# Atom.net
KiCad netlist of a schematic drawn in Altium Designer
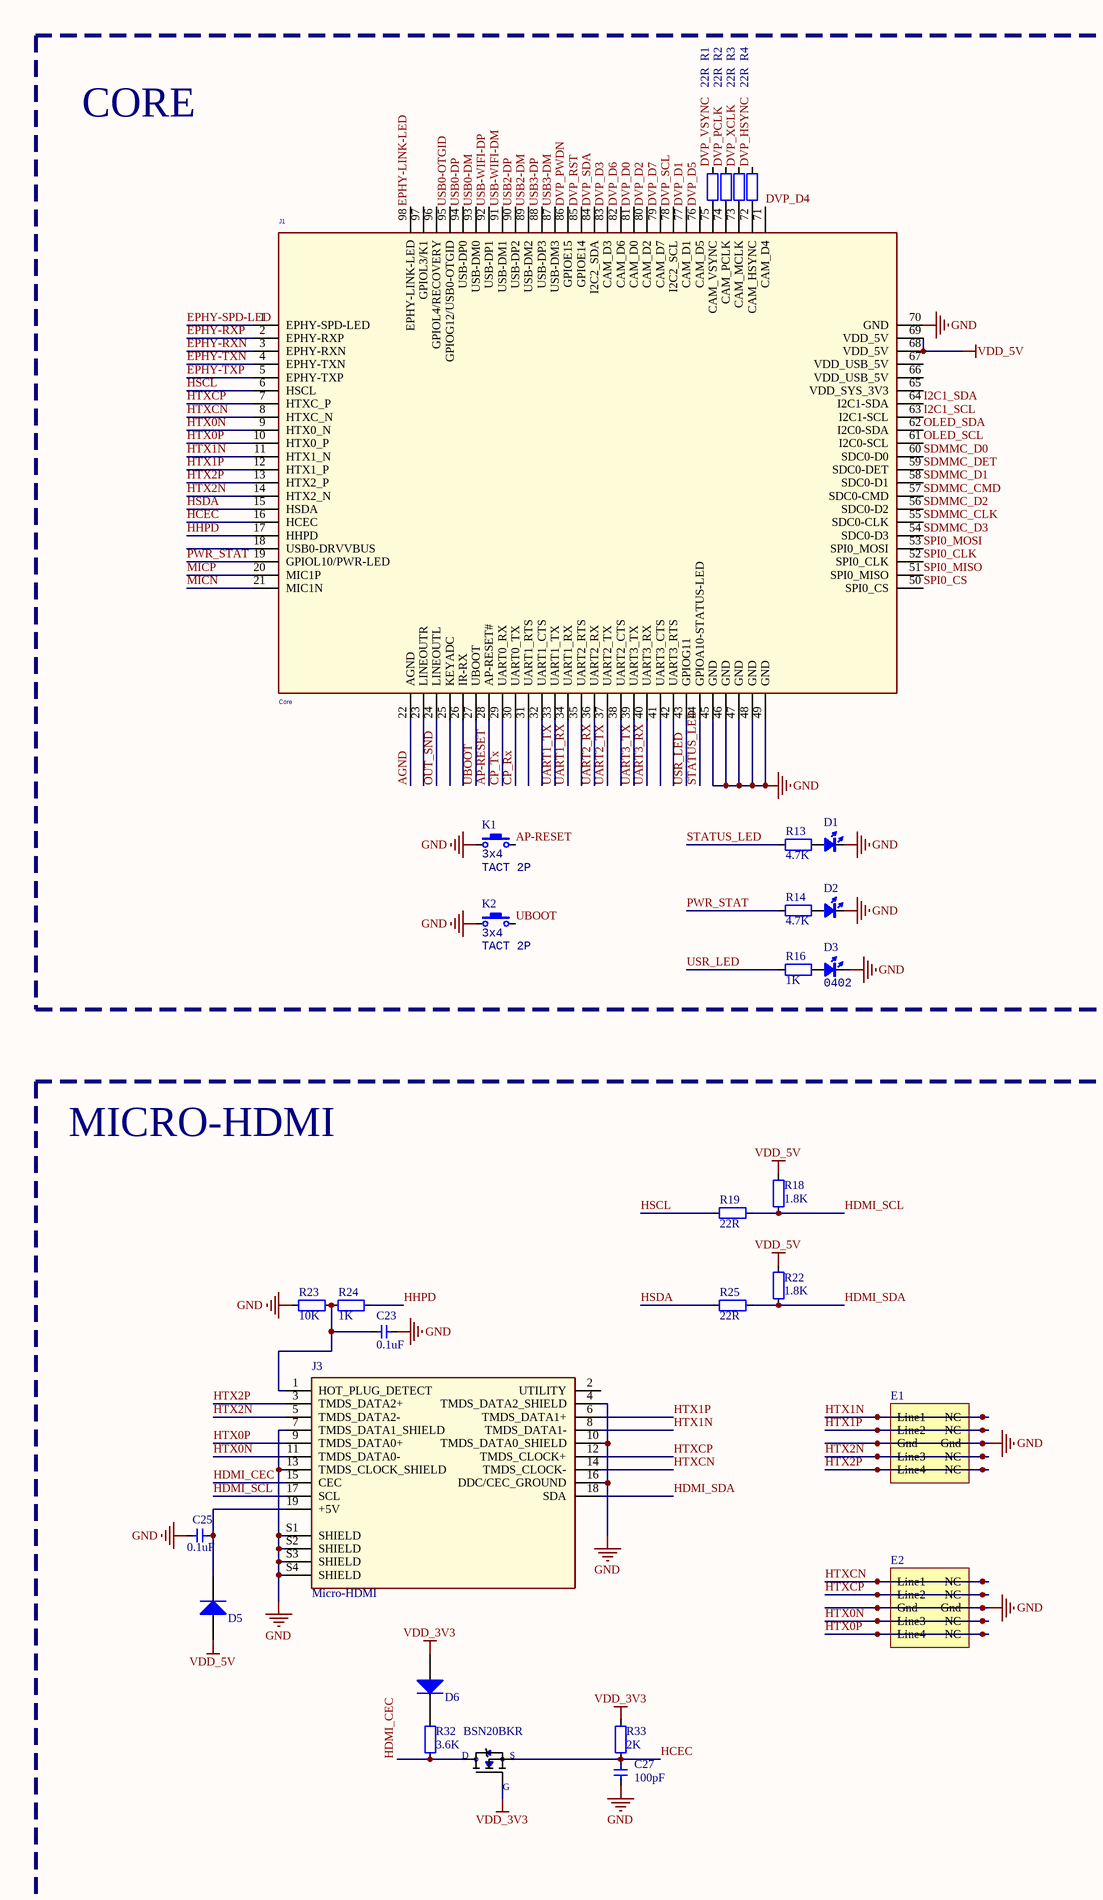
[diagram p0: Atom.SchDoc, left]
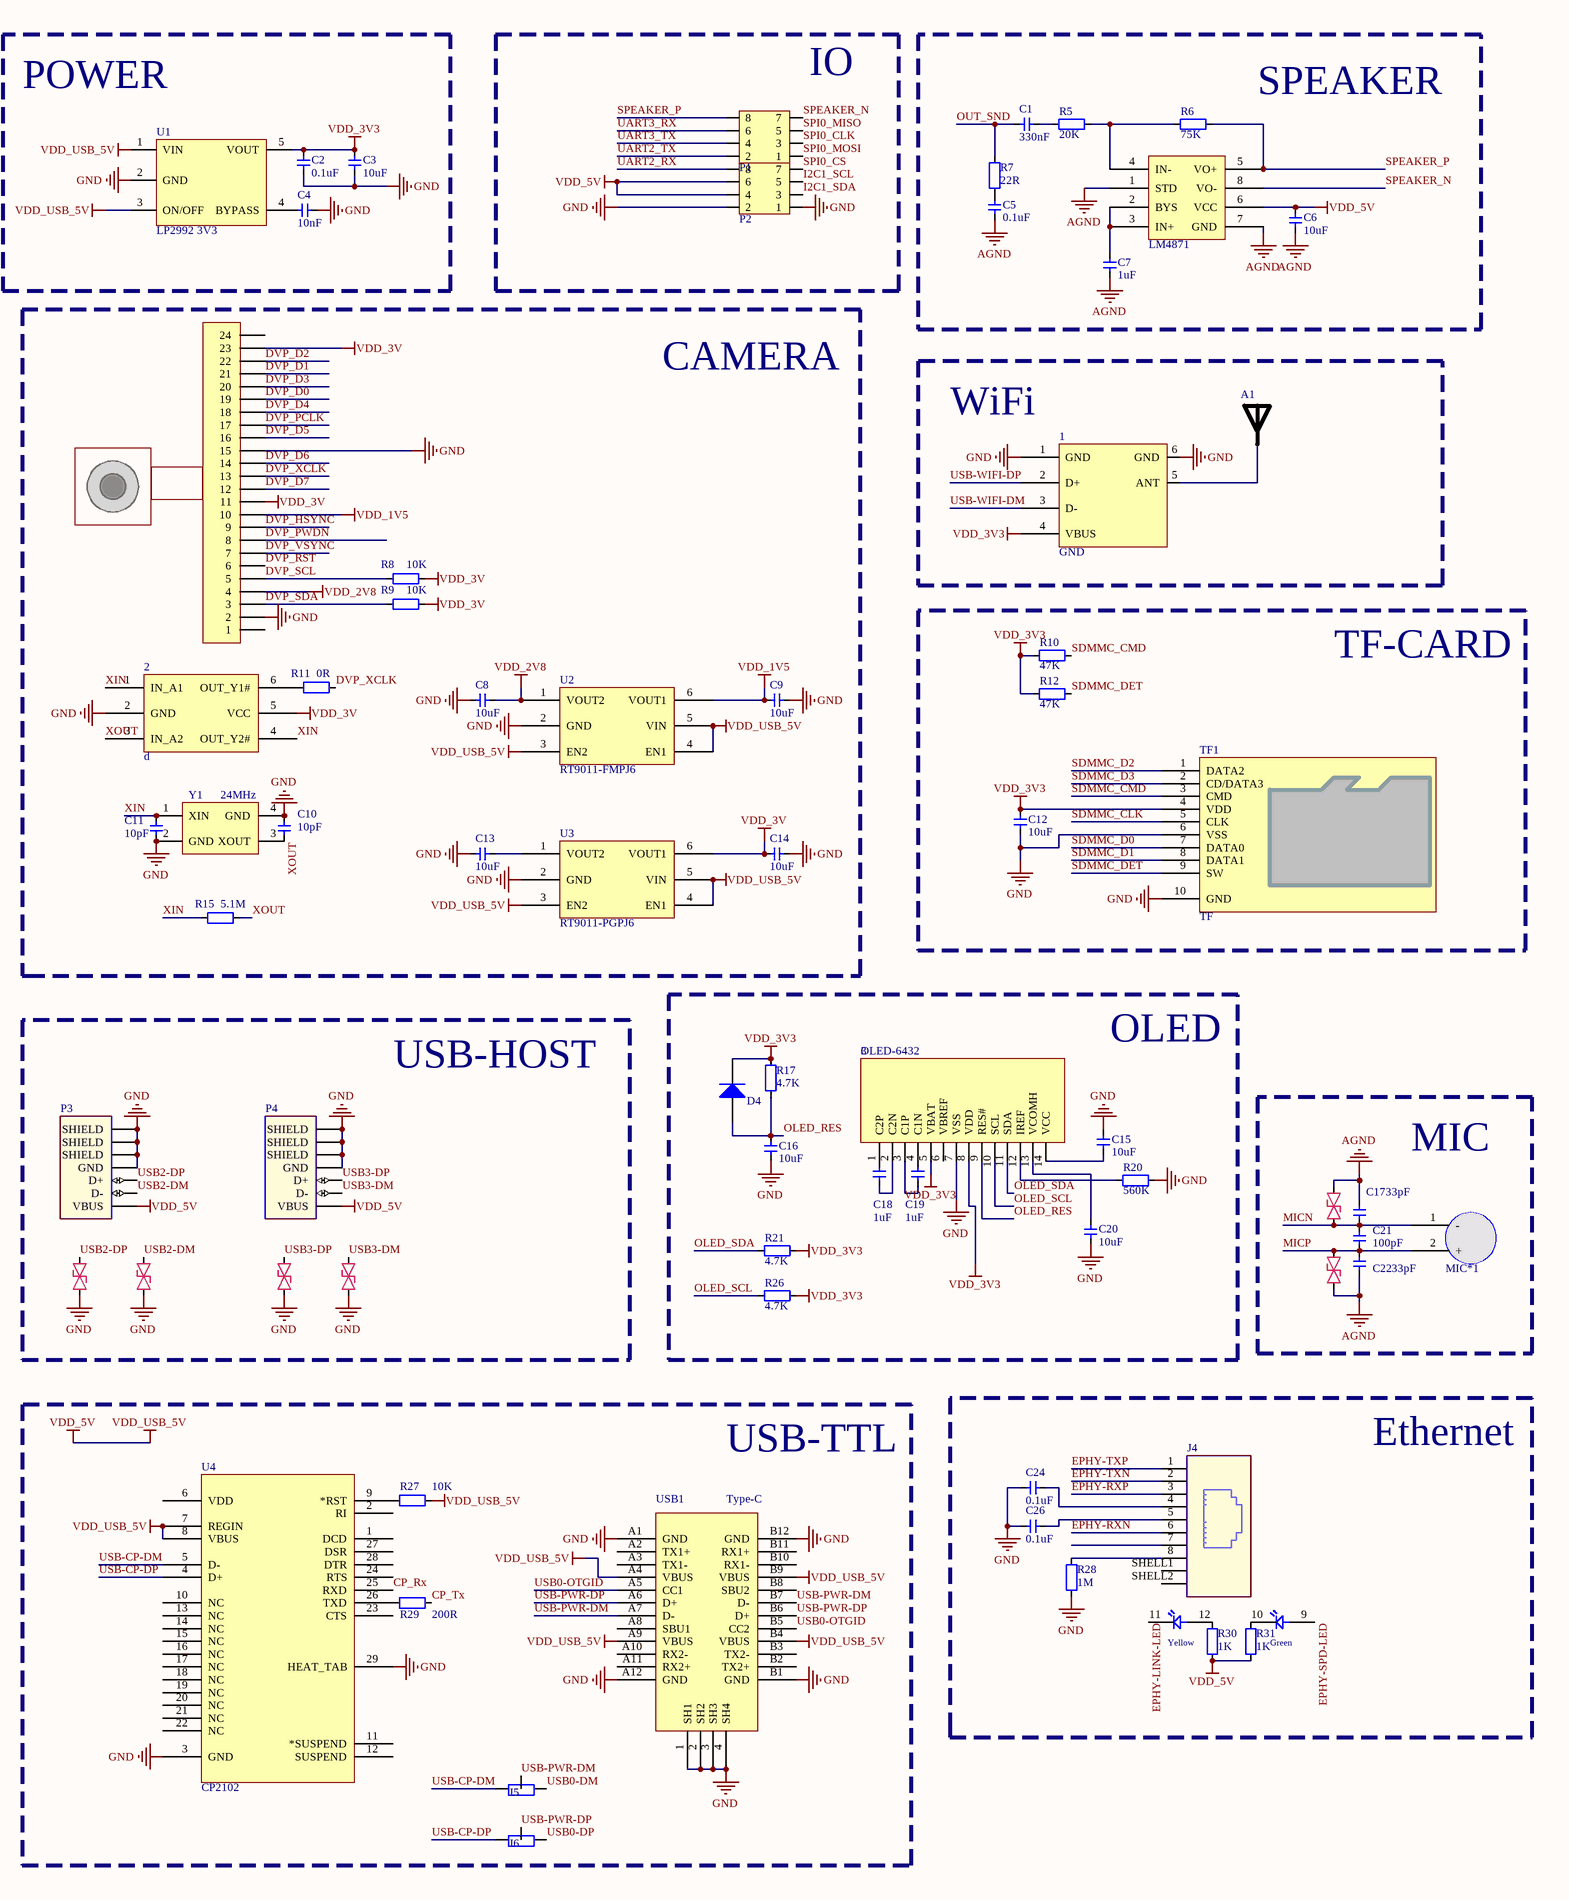
[diagram p1: Atom.SchDoc, right]

(export (version "E")
  (design (tool "Eeschema 10.0.6"))
  (components
    (comp (ref "*1") (value "LM4871") (footprint "MSOP-8") (libsource (lib "MyPcbLib") (part "LM4871")))
    (comp (ref "1")
      (value "GND")
      (footprint "USB-WiFI-ANT")
      (libsource (lib "MyPcbLib") (part "USB-WiFi-ANT"))
    )
    (comp (ref "2") (value "d") (footprint "SOT363-6") (libsource (lib "MyPcbLib") (part "NL27WZU04DF")))
    (comp (ref "3")
      (value "OLED-6432")
      (footprint "OLED-6432-TOP")
      (description "显示屏")
      (libsource (lib "MyPcbLib") (part "OLED-6432"))
    )
    (comp (ref "4")
      (value "BSN20BKR")
      (footprint "SOT23-3")
      (description "N-Channel 60 V 2.8 Ohm 310 mW 0.49 nC Surface Mount Trench MosFet - SOT-23")
      (fields (field (name "MF") "Nexperia USA"))
      (libsource (lib "mLib") (part "BSN20BKR"))
    )
    (comp (ref "A1")
      (value "RAINSUN")
      (footprint "ANT-Rainsun-AN5120")
      (libsource (lib "MyPcbLib") (part "ANT-Rainsun-AP5120"))
    )
    (comp (ref "C1")
      (value "330nF")
      (footprint "0603-CAP")
      (description "Capacitor")
      (libsource (lib "MyPcbLib") (part "电容-0603"))
    )
    (comp (ref "C2")
      (value "0.1uF")
      (footprint "CAP_0402")
      (description "Capacitor")
      (libsource (lib "MyPcbLib") (part "电容-0402"))
    )
    (comp (ref "C3")
      (value "10uF")
      (footprint "CAP_0402")
      (description "Capacitor")
      (libsource (lib "MyPcbLib") (part "电容-0402"))
    )
    (comp (ref "C4")
      (value "10nF")
      (footprint "CAP_0402")
      (description "Capacitor")
      (libsource (lib "MyPcbLib") (part "电容-0402"))
    )
    (comp (ref "C5")
      (value "0.1uF")
      (footprint "CAP_0402")
      (description "Capacitor")
      (libsource (lib "MyPcbLib") (part "电容-0402"))
    )
    (comp (ref "C6")
      (value "10uF")
      (footprint "CAP_0402")
      (description "Capacitor")
      (libsource (lib "MyPcbLib") (part "电容-0402"))
    )
    (comp (ref "C7")
      (value "1uF")
      (footprint "CAP_0402")
      (description "Capacitor")
      (libsource (lib "MyPcbLib") (part "电容-0402"))
    )
    (comp (ref "C8")
      (value "10uF")
      (footprint "CAP_0402")
      (description "Capacitor")
      (libsource (lib "MyPcbLib") (part "电容-0402"))
    )
    (comp (ref "C9")
      (value "10uF")
      (footprint "CAP_0402")
      (description "Capacitor")
      (libsource (lib "MyPcbLib") (part "电容-0402"))
    )
    (comp (ref "C10")
      (value "10pF")
      (footprint "CAP_0402")
      (description "Capacitor")
      (libsource (lib "MyPcbLib") (part "电容-0402"))
    )
    (comp (ref "C11")
      (value "10pF")
      (footprint "CAP_0402")
      (description "Capacitor")
      (libsource (lib "MyPcbLib") (part "电容-0402"))
    )
    (comp (ref "C12")
      (value "10uF")
      (footprint "CAP_0402")
      (description "Capacitor")
      (libsource (lib "MyPcbLib") (part "电容-0402"))
    )
    (comp (ref "C13")
      (value "10uF")
      (footprint "CAP_0402")
      (description "Capacitor")
      (libsource (lib "MyPcbLib") (part "电容-0402"))
    )
    (comp (ref "C14")
      (value "10uF")
      (footprint "CAP_0402")
      (description "Capacitor")
      (libsource (lib "MyPcbLib") (part "电容-0402"))
    )
    (comp (ref "C15")
      (value "10uF")
      (footprint "CAP_0402")
      (description "Capacitor")
      (libsource (lib "MyPcbLib") (part "电容-0402"))
    )
    (comp (ref "C16")
      (value "10uF")
      (footprint "CAP_0402")
      (description "Capacitor")
      (libsource (lib "MyPcbLib") (part "电容-0402"))
    )
    (comp (ref "C17")
      (value "33pF")
      (footprint "CAP_0402")
      (description "Capacitor")
      (libsource (lib "MyPcbLib") (part "电容-0402"))
    )
    (comp (ref "C18")
      (value "1uF")
      (footprint "CAP_0402")
      (description "Capacitor")
      (libsource (lib "MyPcbLib") (part "电容-0402"))
    )
    (comp (ref "C19")
      (value "1uF")
      (footprint "CAP_0402")
      (description "Capacitor")
      (libsource (lib "MyPcbLib") (part "电容-0402"))
    )
    (comp (ref "C20")
      (value "10uF")
      (footprint "CAP_0402")
      (description "Capacitor")
      (libsource (lib "MyPcbLib") (part "电容-0402"))
    )
    (comp (ref "C21")
      (value "100pF")
      (footprint "CAP_0402")
      (description "Capacitor")
      (libsource (lib "MyPcbLib") (part "电容-0402"))
    )
    (comp (ref "C22")
      (value "33pF")
      (footprint "CAP_0402")
      (description "Capacitor")
      (libsource (lib "MyPcbLib") (part "电容-0402"))
    )
    (comp (ref "C23")
      (value "0.1uF")
      (footprint "CAP_0402")
      (description "Capacitor")
      (libsource (lib "MyPcbLib") (part "电容-0402"))
    )
    (comp (ref "C24")
      (value "0.1uF")
      (footprint "CAP_0402")
      (description "Capacitor")
      (libsource (lib "MyPcbLib") (part "电容-0402"))
    )
    (comp (ref "C25")
      (value "0.1uF")
      (footprint "CAP_0402")
      (description "Capacitor")
      (libsource (lib "MyPcbLib") (part "电容-0402"))
    )
    (comp (ref "C26")
      (value "0.1uF")
      (footprint "CAP_0402")
      (description "Capacitor")
      (libsource (lib "MyPcbLib") (part "电容-0402"))
    )
    (comp (ref "C27")
      (value "100pF")
      (footprint "CAP_0402")
      (description "Capacitor")
      (libsource (lib "MyPcbLib") (part "电容-0402"))
    )
    (comp (ref "D1")
      (value "color?")
      (footprint "LED_0402_RED")
      (description "LED")
      (libsource (lib "KitSprout") (part "LED_0402"))
    )
    (comp (ref "D2")
      (value "color?")
      (footprint "LED_0402_RED")
      (description "LED")
      (libsource (lib "KitSprout") (part "LED_0402"))
    )
    (comp (ref "D3")
      (value "color?")
      (footprint "LED_0402_RED")
      (description "LED")
      (fields (field (name "TYPE") "0402"))
      (libsource (lib "KitSprout") (part "LED_0402"))
    )
    (comp (ref "D4")
      (value "二极管-5B5817WS")
      (footprint "SOD-323")
      (description "40V")
      (libsource (lib "MyPcbLib") (part "二极管-5B5817WS"))
    )
    (comp (ref "D5")
      (value "二极管-5B5817WS")
      (footprint "SOD-323")
      (description "40V")
      (libsource (lib "mLib") (part "二极管-5B5817WS"))
    )
    (comp (ref "D6")
      (value "二极管-5B5817WS")
      (footprint "SOD-323")
      (description "40V")
      (libsource (lib "mLib") (part "二极管-5B5817WS"))
    )
    (comp (ref "E1") (value "E?") (footprint "DFN-2510") (libsource (lib "MyPcbLib") (part "AZ1045-04F")))
    (comp (ref "E2") (value "E?") (footprint "DFN-2510") (libsource (lib "MyPcbLib") (part "AZ1045-04F")))
    (comp (ref "ESD-1")
      (value "ESD-0402")
      (footprint "ESD-0402")
      (description "ESD")
      (libsource (lib "MyPcbLib") (part "ESD-0402"))
    )
    (comp (ref "ESD-2")
      (value "ESD-0402")
      (footprint "ESD-0402")
      (description "ESD")
      (libsource (lib "MyPcbLib") (part "ESD-0402"))
    )
    (comp (ref "ESD-3")
      (value "ESD-0402")
      (footprint "ESD-0402")
      (description "ESD")
      (libsource (lib "MyPcbLib") (part "ESD-0402"))
    )
    (comp (ref "ESD-4")
      (value "ESD-0402")
      (footprint "ESD-0402")
      (description "ESD")
      (libsource (lib "MyPcbLib") (part "ESD-0402"))
    )
    (comp (ref "ESD-5")
      (value "ESD-0402")
      (footprint "ESD-0402")
      (description "ESD")
      (libsource (lib "MyPcbLib") (part "ESD-0402"))
    )
    (comp (ref "ESD-6")
      (value "ESD-0402")
      (footprint "ESD-0402")
      (description "ESD")
      (libsource (lib "MyPcbLib") (part "ESD-0402"))
    )
    (comp (ref "J1")
      (value "Core")
      (footprint "Quantum-Quark")
      (libsource (lib "SOM") (part "Quantum-Quark-Core"))
    )
    (comp (ref "J2")
      (value "0.5S_A_24PWB")
      (footprint "FPC-24P")
      (description "Header, 24-Pin")
      (fields (field (name "PUBLISHER") "Altium Limited"))
      (libsource (lib "MyPcbLib") (part "OV2640"))
    )
    (comp (ref "J3")
      (value "Micro-HDMI")
      (footprint "MICRO HDMI")
      (description "Conn Micro HDMI RCP 19 POS 0.4mm Solder RA SMD 19 Terminal 1 Port Micro HDMI Embossed T/R")
      (fields (field (name "MF") "Molex") (field (name "MP") "0467650301"))
      (libsource (lib "MyPcbLib") (part "Micro-HDMI"))
    )
    (comp (ref "J4")
      (value "RJ45座")
      (footprint "RJ45母座")
      (fields (field (name "MF") "Wurth") (field (name "MP") "615008137421"))
      (libsource (lib "mLib") (part "RJ45座"))
    )
    (comp (ref "J5")
      (value "选择跳线")
      (footprint "jumper-3")
      (description "Resistor")
      (fields (field (name "PUBLISHER") "Altium Limited"))
      (libsource (lib "MyPcbLib") (part "选择跳线"))
    )
    (comp (ref "J6")
      (value "选择跳线")
      (footprint "jumper-3")
      (description "Resistor")
      (fields (field (name "PUBLISHER") "Altium Limited"))
      (libsource (lib "MyPcbLib") (part "选择跳线"))
    )
    (comp (ref "K1")
      (value "3x4")
      (footprint "ButtonTACT_3x4x2_180")
      (description "Button")
      (fields (field (name "TYPE") "TACT 2P") (field (name "Comment") "TACT 2P"))
      (libsource (lib "KitSprout") (part "ButtonTACT_3x4x2_180"))
    )
    (comp (ref "K2")
      (value "3x4")
      (footprint "ButtonTACT_3x4x2_180")
      (description "Button")
      (fields (field (name "TYPE") "TACT 2P") (field (name "Comment") "TACT 2P"))
      (libsource (lib "KitSprout") (part "ButtonTACT_3x4x2_180"))
    )
    (comp (ref "MIC*1") (value "MIC*") (footprint "MIC-0416") (libsource (lib "MyPcbLib") (part "MIC")))
    (comp (ref "P1")
      (value "HDR2x4_2.54")
      (footprint "HDR2X4_2.0_180H")
      (description "Header")
      (libsource (lib "mLib") (part "HDR2x4_2.54"))
    )
    (comp (ref "P2")
      (value "HDR2x4_2.54")
      (footprint "HDR2X4_2.0_180H")
      (description "Header")
      (libsource (lib "mLib") (part "HDR2x4_2.54"))
    )
    (comp (ref "P3")
      (value "USB-侧立式")
      (footprint "USB-侧立式")
      (description "USB A Skt, Upright/Flag, R/A GF, W/kinked shell stake, tray")
      (fields (field (name "MF") "Global Connector Technology") (field (name "MP") "USB1025-GF-P-B"))
      (libsource (lib "MyPcbLib") (part "USB-侧立式"))
    )
    (comp (ref "P4")
      (value "USB-侧立式")
      (footprint "USB-侧立式")
      (description "USB A Skt, Upright/Flag, R/A GF, W/kinked shell stake, tray")
      (fields (field (name "MF") "Global Connector Technology") (field (name "MP") "USB1025-GF-P-B"))
      (libsource (lib "MyPcbLib") (part "USB-侧立式"))
    )
    (comp (ref "R1")
      (value "22R")
      (footprint "RES_0402")
      (description "Resistor")
      (libsource (lib "") (part "电阻-0402_3"))
    )
    (comp (ref "R2")
      (value "22R")
      (footprint "RES_0402")
      (description "Resistor")
      (libsource (lib "") (part "电阻-0402_3"))
    )
    (comp (ref "R3")
      (value "22R")
      (footprint "RES_0402")
      (description "Resistor")
      (libsource (lib "") (part "电阻-0402_3"))
    )
    (comp (ref "R4")
      (value "22R")
      (footprint "RES_0402")
      (description "Resistor")
      (libsource (lib "") (part "电阻-0402_3"))
    )
    (comp (ref "R5")
      (value "20K")
      (footprint "RES_0402")
      (description "Resistor")
      (libsource (lib "MyPcbLib") (part "电阻-0402"))
    )
    (comp (ref "R6")
      (value "75K")
      (footprint "RES_0402")
      (description "Resistor")
      (libsource (lib "MyPcbLib") (part "电阻-0402"))
    )
    (comp (ref "R7")
      (value "22R")
      (footprint "RES_0402")
      (description "Resistor")
      (libsource (lib "") (part "电阻-0402_1"))
    )
    (comp (ref "R8")
      (value "10K")
      (footprint "RES_0402")
      (description "Resistor")
      (libsource (lib "MyPcbLib") (part "电阻-0402"))
    )
    (comp (ref "R9")
      (value "10K")
      (footprint "RES_0402")
      (description "Resistor")
      (libsource (lib "MyPcbLib") (part "电阻-0402"))
    )
    (comp (ref "R10")
      (value "47K")
      (footprint "RES_0402")
      (description "Resistor")
      (libsource (lib "MyPcbLib") (part "电阻-0402"))
    )
    (comp (ref "R11")
      (value "0R")
      (footprint "RES_0402")
      (description "Resistor")
      (libsource (lib "MyPcbLib") (part "电阻-0402"))
    )
    (comp (ref "R12")
      (value "47K")
      (footprint "RES_0402")
      (description "Resistor")
      (libsource (lib "MyPcbLib") (part "电阻-0402"))
    )
    (comp (ref "R13")
      (value "4.7K")
      (footprint "RES_0402")
      (description "Resistor")
      (libsource (lib "MyPcbLib") (part "电阻-0402"))
    )
    (comp (ref "R14")
      (value "4.7K")
      (footprint "RES_0402")
      (description "Resistor")
      (libsource (lib "MyPcbLib") (part "电阻-0402"))
    )
    (comp (ref "R15")
      (value "5.1M")
      (footprint "RES_0402")
      (description "Resistor")
      (libsource (lib "MyPcbLib") (part "电阻-0402"))
    )
    (comp (ref "R16")
      (value "1K")
      (footprint "RES_0402")
      (description "Resistor")
      (libsource (lib "MyPcbLib") (part "电阻-0402"))
    )
    (comp (ref "R17")
      (value "4.7K")
      (footprint "RES_0402")
      (description "Resistor")
      (libsource (lib "") (part "电阻-0402_3"))
    )
    (comp (ref "R18")
      (value "1.8K")
      (footprint "RES_0402")
      (description "Resistor")
      (libsource (lib "") (part "电阻-0402_1"))
    )
    (comp (ref "R19")
      (value "22R")
      (footprint "RES_0402")
      (description "Resistor")
      (libsource (lib "MyPcbLib") (part "电阻-0402"))
    )
    (comp (ref "R20")
      (value "560K")
      (footprint "RES_0402")
      (description "Resistor")
      (libsource (lib "") (part "电阻-0402_2"))
    )
    (comp (ref "R21")
      (value "4.7K")
      (footprint "RES_0402")
      (description "Resistor")
      (libsource (lib "MyPcbLib") (part "电阻-0402"))
    )
    (comp (ref "R22")
      (value "1.8K")
      (footprint "RES_0402")
      (description "Resistor")
      (libsource (lib "") (part "电阻-0402_1"))
    )
    (comp (ref "R23")
      (value "10K")
      (footprint "RES_0402")
      (description "Resistor")
      (libsource (lib "MyPcbLib") (part "电阻-0402"))
    )
    (comp (ref "R24")
      (value "1K")
      (footprint "RES_0402")
      (description "Resistor")
      (libsource (lib "MyPcbLib") (part "电阻-0402"))
    )
    (comp (ref "R25")
      (value "22R")
      (footprint "RES_0402")
      (description "Resistor")
      (libsource (lib "MyPcbLib") (part "电阻-0402"))
    )
    (comp (ref "R26")
      (value "4.7K")
      (footprint "RES_0402")
      (description "Resistor")
      (libsource (lib "MyPcbLib") (part "电阻-0402"))
    )
    (comp (ref "R27")
      (value "10K")
      (footprint "RES_0402")
      (description "Resistor")
      (libsource (lib "") (part "电阻-0402_2"))
    )
    (comp (ref "R28")
      (value "1M")
      (footprint "RES_0402")
      (description "Resistor")
      (libsource (lib "") (part "电阻-0402_1"))
    )
    (comp (ref "R29")
      (value "200R")
      (footprint "RES_0402")
      (description "Resistor")
      (libsource (lib "") (part "电阻-0402_2"))
    )
    (comp (ref "R30")
      (value "1K")
      (footprint "RES_0402")
      (description "Resistor")
      (libsource (lib "") (part "电阻-0402_1"))
    )
    (comp (ref "R31")
      (value "1K")
      (footprint "RES_0402")
      (description "Resistor")
      (libsource (lib "") (part "电阻-0402_1"))
    )
    (comp (ref "R32")
      (value "3.6K")
      (footprint "RES_0402")
      (description "Resistor")
      (libsource (lib "") (part "电阻-0402_1"))
    )
    (comp (ref "R33")
      (value "2K")
      (footprint "RES_0402")
      (description "Resistor")
      (libsource (lib "") (part "电阻-0402_1"))
    )
    (comp (ref "TF1")
      (value "TF")
      (footprint "TF-SOCKET - short")
      (description "8脚自弹")
      (libsource (lib "MyPcbLib") (part "TF卡座"))
    )
    (comp (ref "U1")
      (value "LP2992 3V3")
      (footprint "SOT23-5")
      (description "LDO")
      (libsource (lib "MyPcbLib") (part "LP2992"))
    )
    (comp (ref "U2") (value "RT9011-FMPJ6") (footprint "SOT23-6") (libsource (lib "mLib") (part "RT9011")))
    (comp (ref "U3") (value "RT9011-PGPJ6") (footprint "SOT23-6") (libsource (lib "mLib") (part "RT9011")))
    (comp (ref "U4")
      (value "CP2102")
      (footprint "QFN-28")
      (description "USB转TTL")
      (libsource (lib "mLib") (part "CP2102"))
    )
    (comp (ref "USB1")
      (value "Type-C")
      (footprint "Type-C-TOP")
      (libsource (lib "MyPcbLib") (part "USB-Type-C-TOP"))
    )
    (comp (ref "Y1")
      (value "24MHz")
      (footprint "晶振2520")
      (description "2520无源")
      (fields (field (name "MF") "ECS International") (field (name "MP") "ECS-3225S30-240-EN-TR"))
      (libsource (lib "MyPcbLib") (part "晶振-4Pin-无源"))
    )
  )
  (nets
    (net (code "1") (name "/AP-RESET") (class "Default")
      (node (ref "J1") (pin "28") (pinfunction "AP-RESET#_28") (pintype "passive"))
      (node (ref "K1") (pin "2") (pinfunction "2_2") (pintype "passive"))
    )
    (net (code "2") (name "/CP_Rx") (class "Default")
      (node (ref "J1") (pin "30") (pinfunction "UART0_TX_30") (pintype "passive"))
      (node (ref "U4") (pin "25") (pinfunction "RXD_25") (pintype "passive"))
    )
    (net (code "3") (name "/CP_Tx") (class "Default")
      (node (ref "J1") (pin "29") (pinfunction "UART0_RX_29") (pintype "passive"))
      (node (ref "R29") (pin "1") (pinfunction "1_1") (pintype "passive"))
    )
    (net (code "4") (name "/DVP_D0") (class "Default")
      (node (ref "J1") (pin "81") (pinfunction "CAM_D0_81") (pintype "passive"))
      (node (ref "J2") (pin "19") (pinfunction "19_19") (pintype "passive"))
    )
    (net (code "5") (name "/DVP_D1") (class "Default")
      (node (ref "J1") (pin "77") (pinfunction "CAM_D1_77") (pintype "passive"))
      (node (ref "J2") (pin "21") (pinfunction "21_21") (pintype "passive"))
    )
    (net (code "6") (name "/DVP_D2") (class "Default")
      (node (ref "J1") (pin "80") (pinfunction "CAM_D2_80") (pintype "passive"))
      (node (ref "J2") (pin "22") (pinfunction "22_22") (pintype "passive"))
    )
    (net (code "7") (name "/DVP_D3") (class "Default")
      (node (ref "J1") (pin "83") (pinfunction "CAM_D3_83") (pintype "passive"))
      (node (ref "J2") (pin "20") (pinfunction "20_20") (pintype "passive"))
    )
    (net (code "8") (name "/DVP_D4") (class "Default")
      (node (ref "J1") (pin "71") (pinfunction "CAM_D4_71") (pintype "passive"))
      (node (ref "J2") (pin "18") (pinfunction "18_18") (pintype "passive"))
    )
    (net (code "9") (name "/DVP_D5") (class "Default")
      (node (ref "J1") (pin "76") (pinfunction "CAM_D5_76") (pintype "passive"))
      (node (ref "J2") (pin "16") (pinfunction "16_16") (pintype "passive"))
    )
    (net (code "10") (name "/DVP_D6") (class "Default")
      (node (ref "J1") (pin "82") (pinfunction "CAM_D6_82") (pintype "passive"))
      (node (ref "J2") (pin "14") (pinfunction "14_14") (pintype "passive"))
    )
    (net (code "11") (name "/DVP_D7") (class "Default")
      (node (ref "J1") (pin "79") (pinfunction "CAM_D7_79") (pintype "passive"))
      (node (ref "J2") (pin "12") (pinfunction "12_12") (pintype "passive"))
    )
    (net (code "12") (name "/DVP_HSYNC") (class "Default")
      (node (ref "J2") (pin "9") (pinfunction "9_9") (pintype "passive"))
      (node (ref "R4") (pin "1") (pinfunction "1_1") (pintype "passive"))
    )
    (net (code "13") (name "/DVP_PCLK") (class "Default")
      (node (ref "J2") (pin "17") (pinfunction "17_17") (pintype "passive"))
      (node (ref "R2") (pin "1") (pinfunction "1_1") (pintype "passive"))
    )
    (net (code "14") (name "/DVP_PWDN") (class "Default")
      (node (ref "J1") (pin "86") (pinfunction "GPIOE15_86") (pintype "passive"))
      (node (ref "J2") (pin "8") (pinfunction "8_8") (pintype "passive"))
    )
    (net (code "15") (name "/DVP_RST") (class "Default")
      (node (ref "J1") (pin "85") (pinfunction "GPIOE14_85") (pintype "passive"))
      (node (ref "J2") (pin "6") (pinfunction "6_6") (pintype "passive"))
    )
    (net (code "16") (name "/DVP_SCL") (class "Default")
      (node (ref "J1") (pin "78") (pinfunction "I2C2_SCL_78") (pintype "passive"))
      (node (ref "J2") (pin "5") (pinfunction "5_5") (pintype "passive"))
      (node (ref "R8") (pin "1") (pinfunction "1_1") (pintype "passive"))
    )
    (net (code "17") (name "/DVP_SDA") (class "Default")
      (node (ref "J1") (pin "84") (pinfunction "I2C2_SDA_84") (pintype "passive"))
      (node (ref "J2") (pin "3") (pinfunction "3_3") (pintype "passive"))
      (node (ref "R9") (pin "1") (pinfunction "1_1") (pintype "passive"))
    )
    (net (code "18") (name "/DVP_VSYNC") (class "Default")
      (node (ref "J2") (pin "7") (pinfunction "7_7") (pintype "passive"))
      (node (ref "R1") (pin "1") (pinfunction "1_1") (pintype "passive"))
    )
    (net (code "19") (name "/DVP_XCLK") (class "Default")
      (node (ref "J2") (pin "13") (pinfunction "13_13") (pintype "passive"))
      (node (ref "R11") (pin "2") (pinfunction "2_2") (pintype "passive"))
      (node (ref "R3") (pin "1") (pinfunction "1_1") (pintype "passive"))
    )
    (net (code "20") (name "/EPHY-LINK-LED") (class "Default")
      (node (ref "J1") (pin "98") (pinfunction "EPHY-LINK-LED_98") (pintype "passive"))
      (node (ref "J4") (pin "11") (pinfunction "10_11") (pintype "passive"))
    )
    (net (code "21") (name "/EPHY-RXN") (class "Default")
      (node (ref "J1") (pin "3") (pinfunction "EPHY-RXN_3") (pintype "passive"))
      (node (ref "J4") (pin "6") (pinfunction "3_6") (pintype "passive"))
    )
    (net (code "22") (name "/EPHY-RXP") (class "Default")
      (node (ref "J1") (pin "2") (pinfunction "EPHY-RXP_2") (pintype "passive"))
      (node (ref "J4") (pin "3") (pinfunction "6_3") (pintype "passive"))
    )
    (net (code "23") (name "/EPHY-SPD-LED") (class "Default")
      (node (ref "J1") (pin "1") (pinfunction "EPHY-SPD-LED_1") (pintype "passive"))
      (node (ref "J4") (pin "9") (pinfunction "12_9") (pintype "passive"))
    )
    (net (code "24") (name "/EPHY-TXN") (class "Default")
      (node (ref "J1") (pin "4") (pinfunction "EPHY-TXN_4") (pintype "passive"))
      (node (ref "J4") (pin "2") (pinfunction "7_2") (pintype "passive"))
    )
    (net (code "25") (name "/EPHY-TXP") (class "Default")
      (node (ref "J1") (pin "5") (pinfunction "EPHY-TXP_5") (pintype "passive"))
      (node (ref "J4") (pin "1") (pinfunction "8_1") (pintype "passive"))
    )
    (net (code "26") (name "/HCEC") (class "Default")
      (node (ref "4") (pin "2") (pinfunction "S_2") (pintype "passive"))
      (node (ref "C27") (pin "2") (pinfunction "2_2") (pintype "passive"))
      (node (ref "J1") (pin "16") (pinfunction "HCEC_16") (pintype "passive"))
      (node (ref "R33") (pin "1") (pinfunction "1_1") (pintype "passive"))
    )
    (net (code "27") (name "/HDMI_CEC") (class "Default")
      (node (ref "4") (pin "3") (pinfunction "D_3") (pintype "passive"))
      (node (ref "J3") (pin "15") (pinfunction "CEC_15") (pintype "passive"))
      (node (ref "R32") (pin "1") (pinfunction "1_1") (pintype "passive"))
    )
    (net (code "28") (name "/HDMI_SCL") (class "Default")
      (node (ref "J3") (pin "17") (pinfunction "SCL_17") (pintype "passive"))
      (node (ref "R18") (pin "1") (pinfunction "1_1") (pintype "passive"))
      (node (ref "R19") (pin "2") (pinfunction "2_2") (pintype "passive"))
    )
    (net (code "29") (name "/HDMI_SDA") (class "Default")
      (node (ref "J3") (pin "18") (pinfunction "SDA_18") (pintype "passive"))
      (node (ref "R22") (pin "1") (pinfunction "1_1") (pintype "passive"))
      (node (ref "R25") (pin "2") (pinfunction "2_2") (pintype "passive"))
    )
    (net (code "30") (name "/HHPD") (class "Default")
      (node (ref "J1") (pin "17") (pinfunction "HHPD_17") (pintype "passive"))
      (node (ref "R24") (pin "2") (pinfunction "2_2") (pintype "passive"))
    )
    (net (code "31") (name "/HSCL") (class "Default")
      (node (ref "J1") (pin "6") (pinfunction "HSCL_6") (pintype "passive"))
      (node (ref "R19") (pin "1") (pinfunction "1_1") (pintype "passive"))
    )
    (net (code "32") (name "/HSDA") (class "Default")
      (node (ref "J1") (pin "15") (pinfunction "HSDA_15") (pintype "passive"))
      (node (ref "R25") (pin "1") (pinfunction "1_1") (pintype "passive"))
    )
    (net (code "33") (name "/HTX0N") (class "Default")
      (node (ref "E2") (pin "4") (pinfunction "Line3_4") (pintype "passive"))
      (node (ref "E2") (pin "7") (pinfunction "NC_7") (pintype "passive"))
      (node (ref "J1") (pin "9") (pinfunction "HTX0_N_9") (pintype "passive"))
      (node (ref "J3") (pin "11") (pinfunction "TMDS_DATA0-_11") (pintype "passive"))
    )
    (net (code "34") (name "/HTX0P") (class "Default")
      (node (ref "E2") (pin "5") (pinfunction "Line4_5") (pintype "passive"))
      (node (ref "E2") (pin "6") (pinfunction "NC_6") (pintype "passive"))
      (node (ref "J1") (pin "10") (pinfunction "HTX0_P_10") (pintype "passive"))
      (node (ref "J3") (pin "9") (pinfunction "TMDS_DATA0+_9") (pintype "passive"))
    )
    (net (code "35") (name "/HTX1N") (class "Default")
      (node (ref "E1") (pin "1") (pinfunction "Line1_1") (pintype "passive"))
      (node (ref "E1") (pin "10") (pinfunction "NC_10") (pintype "passive"))
      (node (ref "J1") (pin "11") (pinfunction "HTX1_N_11") (pintype "passive"))
      (node (ref "J3") (pin "8") (pinfunction "TMDS_DATA1-_8") (pintype "passive"))
    )
    (net (code "36") (name "/HTX1P") (class "Default")
      (node (ref "E1") (pin "2") (pinfunction "Line2_2") (pintype "passive"))
      (node (ref "E1") (pin "9") (pinfunction "NC_9") (pintype "passive"))
      (node (ref "J1") (pin "12") (pinfunction "HTX1_P_12") (pintype "passive"))
      (node (ref "J3") (pin "6") (pinfunction "TMDS_DATA1+_6") (pintype "passive"))
    )
    (net (code "37") (name "/HTX2N") (class "Default")
      (node (ref "E1") (pin "4") (pinfunction "Line3_4") (pintype "passive"))
      (node (ref "E1") (pin "7") (pinfunction "NC_7") (pintype "passive"))
      (node (ref "J1") (pin "14") (pinfunction "HTX2_N_14") (pintype "passive"))
      (node (ref "J3") (pin "5") (pinfunction "TMDS_DATA2-_5") (pintype "passive"))
    )
    (net (code "38") (name "/HTX2P") (class "Default")
      (node (ref "E1") (pin "5") (pinfunction "Line4_5") (pintype "passive"))
      (node (ref "E1") (pin "6") (pinfunction "NC_6") (pintype "passive"))
      (node (ref "J1") (pin "13") (pinfunction "HTX2_P_13") (pintype "passive"))
      (node (ref "J3") (pin "3") (pinfunction "TMDS_DATA2+_3") (pintype "passive"))
    )
    (net (code "39") (name "/HTXCN") (class "Default")
      (node (ref "E2") (pin "1") (pinfunction "Line1_1") (pintype "passive"))
      (node (ref "E2") (pin "10") (pinfunction "NC_10") (pintype "passive"))
      (node (ref "J1") (pin "8") (pinfunction "HTXC_N_8") (pintype "passive"))
      (node (ref "J3") (pin "14") (pinfunction "TMDS_CLOCK-_14") (pintype "passive"))
    )
    (net (code "40") (name "/HTXCP") (class "Default")
      (node (ref "E2") (pin "2") (pinfunction "Line2_2") (pintype "passive"))
      (node (ref "E2") (pin "9") (pinfunction "NC_9") (pintype "passive"))
      (node (ref "J1") (pin "7") (pinfunction "HTXC_P_7") (pintype "passive"))
      (node (ref "J3") (pin "12") (pinfunction "TMDS_CLOCK+_12") (pintype "passive"))
    )
    (net (code "41") (name "/I2C1_SCL") (class "Default")
      (node (ref "J1") (pin "63") (pinfunction "I2C1-SCL_63") (pintype "passive"))
      (node (ref "P2") (pin "5") (pinfunction "5_5") (pintype "passive"))
    )
    (net (code "42") (name "/I2C1_SDA") (class "Default")
      (node (ref "J1") (pin "64") (pinfunction "I2C1-SDA_64") (pintype "passive"))
      (node (ref "P2") (pin "3") (pinfunction "3_3") (pintype "passive"))
    )
    (net (code "43") (name "/MICN") (class "Default")
      (node (ref "C17") (pin "2") (pinfunction "2_2") (pintype "passive"))
      (node (ref "C21") (pin "2") (pinfunction "2_2") (pintype "passive"))
      (node (ref "ESD-1") (pin "1") (pinfunction "1_1") (pintype "passive"))
      (node (ref "J1") (pin "21") (pinfunction "MIC1N_21") (pintype "passive"))
      (node (ref "MIC*1") (pin "1") (pinfunction "-_1") (pintype "passive"))
    )
    (net (code "44") (name "/MICP") (class "Default")
      (node (ref "C21") (pin "1") (pinfunction "1_1") (pintype "passive"))
      (node (ref "C22") (pin "2") (pinfunction "2_2") (pintype "passive"))
      (node (ref "ESD-2") (pin "2") (pinfunction "2_2") (pintype "passive"))
      (node (ref "J1") (pin "20") (pinfunction "MIC1P_20") (pintype "passive"))
      (node (ref "MIC*1") (pin "2") (pinfunction "+_2") (pintype "passive"))
    )
    (net (code "45") (name "/OLED_RES") (class "Default")
      (node (ref "3") (pin "9") (pinfunction "RES#_9") (pintype "passive"))
      (node (ref "C16") (pin "2") (pinfunction "2_2") (pintype "passive"))
      (node (ref "D4") (pin "1") (pinfunction "A_1") (pintype "passive"))
      (node (ref "R17") (pin "2") (pinfunction "2_2") (pintype "passive"))
    )
    (net (code "46") (name "/OLED_SCL") (class "Default")
      (node (ref "3") (pin "10") (pinfunction "SCL_10") (pintype "passive"))
      (node (ref "J1") (pin "61") (pinfunction "I2C0-SCL_61") (pintype "passive"))
      (node (ref "R26") (pin "1") (pinfunction "1_1") (pintype "passive"))
    )
    (net (code "47") (name "/OLED_SDA") (class "Default")
      (node (ref "3") (pin "11") (pinfunction "SDA_11") (pintype "passive"))
      (node (ref "J1") (pin "62") (pinfunction "I2C0-SDA_62") (pintype "passive"))
      (node (ref "R21") (pin "1") (pinfunction "1_1") (pintype "passive"))
    )
    (net (code "48") (name "/OUT_SND") (class "Default")
      (node (ref "C1") (pin "2") (pinfunction "2_2") (pintype "passive"))
      (node (ref "J1") (pin "24") (pinfunction "LINEOUTL_24") (pintype "passive"))
      (node (ref "R7") (pin "2") (pinfunction "2_2") (pintype "passive"))
    )
    (net (code "49") (name "/PWR_STAT") (class "Default")
      (node (ref "J1") (pin "19") (pinfunction "GPIOL10/PWR-LED_19") (pintype "passive"))
      (node (ref "R14") (pin "1") (pinfunction "1_1") (pintype "passive"))
    )
    (net (code "50") (name "/SDMMC_CLK") (class "Default")
      (node (ref "J1") (pin "55") (pinfunction "SDC0-CLK_55") (pintype "passive"))
      (node (ref "TF1") (pin "5") (pinfunction "CLK_5") (pintype "passive"))
    )
    (net (code "51") (name "/SDMMC_CMD") (class "Default")
      (node (ref "J1") (pin "57") (pinfunction "SDC0-CMD_57") (pintype "passive"))
      (node (ref "R10") (pin "2") (pinfunction "2_2") (pintype "passive"))
      (node (ref "TF1") (pin "3") (pinfunction "CMD_3") (pintype "passive"))
    )
    (net (code "52") (name "/SDMMC_D0") (class "Default")
      (node (ref "J1") (pin "60") (pinfunction "SDC0-D0_60") (pintype "passive"))
      (node (ref "TF1") (pin "7") (pinfunction "DATA0_7") (pintype "passive"))
    )
    (net (code "53") (name "/SDMMC_D1") (class "Default")
      (node (ref "J1") (pin "58") (pinfunction "SDC0-D1_58") (pintype "passive"))
      (node (ref "TF1") (pin "8") (pinfunction "DATA1_8") (pintype "passive"))
    )
    (net (code "54") (name "/SDMMC_D2") (class "Default")
      (node (ref "J1") (pin "56") (pinfunction "SDC0-D2_56") (pintype "passive"))
      (node (ref "TF1") (pin "1") (pinfunction "DATA2_1") (pintype "passive"))
    )
    (net (code "55") (name "/SDMMC_D3") (class "Default")
      (node (ref "J1") (pin "54") (pinfunction "SDC0-D3_54") (pintype "passive"))
      (node (ref "TF1") (pin "2") (pinfunction "CD/DATA3_2") (pintype "passive"))
    )
    (net (code "56") (name "/SDMMC_DET") (class "Default")
      (node (ref "J1") (pin "59") (pinfunction "SDC0-DET_59") (pintype "passive"))
      (node (ref "R12") (pin "2") (pinfunction "2_2") (pintype "passive"))
      (node (ref "TF1") (pin "9") (pinfunction "SW_9") (pintype "passive"))
    )
    (net (code "57") (name "/SPEAKER_N") (class "Default")
      (node (ref "*1") (pin "8") (pinfunction "VO-_8") (pintype "passive"))
      (node (ref "P1") (pin "7") (pinfunction "7_7") (pintype "passive"))
    )
    (net (code "58") (name "/SPEAKER_P") (class "Default")
      (node (ref "*1") (pin "5") (pinfunction "VO+_5") (pintype "passive"))
      (node (ref "P1") (pin "8") (pinfunction "8_8") (pintype "passive"))
      (node (ref "R6") (pin "2") (pinfunction "2_2") (pintype "passive"))
    )
    (net (code "59") (name "/SPI0_CLK") (class "Default")
      (node (ref "J1") (pin "52") (pinfunction "SPI0_CLK_52") (pintype "passive"))
      (node (ref "P1") (pin "3") (pinfunction "3_3") (pintype "passive"))
    )
    (net (code "60") (name "/SPI0_CS") (class "Default")
      (node (ref "J1") (pin "50") (pinfunction "SPI0_CS_50") (pintype "passive"))
      (node (ref "P2") (pin "7") (pinfunction "7_7") (pintype "passive"))
    )
    (net (code "61") (name "/SPI0_MISO") (class "Default")
      (node (ref "J1") (pin "51") (pinfunction "SPI0_MISO_51") (pintype "passive"))
      (node (ref "P1") (pin "5") (pinfunction "5_5") (pintype "passive"))
    )
    (net (code "62") (name "/SPI0_MOSI") (class "Default")
      (node (ref "J1") (pin "53") (pinfunction "SPI0_MOSI_53") (pintype "passive"))
      (node (ref "P1") (pin "1") (pinfunction "1_1") (pintype "passive"))
    )
    (net (code "63") (name "/STATUS_LED") (class "Default")
      (node (ref "J1") (pin "44") (pinfunction "GPIOA10-STATUS-LED_44") (pintype "passive"))
      (node (ref "R13") (pin "1") (pinfunction "1_1") (pintype "passive"))
    )
    (net (code "64") (name "/UART1_RX") (class "Default")
      (node (ref "J1") (pin "34") (pinfunction "UART1_RX_34") (pintype "passive"))
    )
    (net (code "65") (name "/UART1_TX") (class "Default")
      (node (ref "J1") (pin "33") (pinfunction "UART1_TX_33") (pintype "passive"))
    )
    (net (code "66") (name "/UART2_RX") (class "Default")
      (node (ref "J1") (pin "36") (pinfunction "UART2_RX_36") (pintype "passive"))
      (node (ref "P2") (pin "8") (pinfunction "8_8") (pintype "passive"))
    )
    (net (code "67") (name "/UART2_TX") (class "Default")
      (node (ref "J1") (pin "37") (pinfunction "UART2_TX_37") (pintype "passive"))
      (node (ref "P1") (pin "2") (pinfunction "2_2") (pintype "passive"))
    )
    (net (code "68") (name "/UART3_RX") (class "Default")
      (node (ref "J1") (pin "40") (pinfunction "UART3_RX_40") (pintype "passive"))
      (node (ref "P1") (pin "6") (pinfunction "6_6") (pintype "passive"))
    )
    (net (code "69") (name "/UART3_TX") (class "Default")
      (node (ref "J1") (pin "39") (pinfunction "UART3_TX_39") (pintype "passive"))
      (node (ref "P1") (pin "4") (pinfunction "4_4") (pintype "passive"))
    )
    (net (code "70") (name "/UBOOT") (class "Default")
      (node (ref "J1") (pin "27") (pinfunction "UBOOT_27") (pintype "passive"))
      (node (ref "K2") (pin "2") (pinfunction "2_2") (pintype "passive"))
    )
    (net (code "71") (name "/USB-CP-DM") (class "Default")
      (node (ref "J5") (pin "1") (pinfunction "1_1") (pintype "passive"))
      (node (ref "U4") (pin "5") (pinfunction "D-_5") (pintype "passive"))
    )
    (net (code "72") (name "/USB-CP-DP") (class "Default")
      (node (ref "J6") (pin "1") (pinfunction "1_1") (pintype "passive"))
      (node (ref "U4") (pin "4") (pinfunction "D+_4") (pintype "passive"))
    )
    (net (code "73") (name "/USB-PWR-DM") (class "Default")
      (node (ref "J5") (pin "2") (pinfunction "2_2") (pintype "passive"))
      (node (ref "USB1") (pin "A7") (pinfunction "D-_A7") (pintype "passive"))
      (node (ref "USB1") (pin "B7") (pinfunction "D-_B7") (pintype "passive"))
    )
    (net (code "74") (name "/USB-PWR-DP") (class "Default")
      (node (ref "J6") (pin "2") (pinfunction "2_2") (pintype "passive"))
      (node (ref "USB1") (pin "A6") (pinfunction "D+_A6") (pintype "passive"))
      (node (ref "USB1") (pin "B6") (pinfunction "D+_B6") (pintype "passive"))
    )
    (net (code "75") (name "/USB-WIFI-DM") (class "Default")
      (node (ref "1") (pin "3") (pinfunction "D-_3") (pintype "passive"))
      (node (ref "J1") (pin "91") (pinfunction "USB-DM1_91") (pintype "passive"))
    )
    (net (code "76") (name "/USB-WIFI-DP") (class "Default")
      (node (ref "1") (pin "2") (pinfunction "D+_2") (pintype "passive"))
      (node (ref "J1") (pin "92") (pinfunction "USB-DP1_92") (pintype "passive"))
    )
    (net (code "77") (name "/USB0-DM") (class "Default")
      (node (ref "J1") (pin "93") (pinfunction "USB-DM0_93") (pintype "passive"))
      (node (ref "J5") (pin "3") (pinfunction "3_3") (pintype "passive"))
    )
    (net (code "78") (name "/USB0-DP") (class "Default")
      (node (ref "J1") (pin "94") (pinfunction "USB-DP0_94") (pintype "passive"))
      (node (ref "J6") (pin "3") (pinfunction "3_3") (pintype "passive"))
    )
    (net (code "79") (name "/USB0-OTGID") (class "Default")
      (node (ref "J1") (pin "95") (pinfunction "GPIOG12/USB0-OTGID_95") (pintype "passive"))
      (node (ref "USB1") (pin "A5") (pinfunction "CC1_A5") (pintype "passive"))
      (node (ref "USB1") (pin "B5") (pinfunction "CC2_B5") (pintype "passive"))
    )
    (net (code "80") (name "/USB2-DM") (class "Default")
      (node (ref "ESD-4") (pin "2") (pinfunction "2_2") (pintype "passive"))
      (node (ref "J1") (pin "89") (pinfunction "USB-DM2_89") (pintype "passive"))
      (node (ref "P3") (pin "2") (pinfunction "D-_2") (pintype "bidirectional"))
    )
    (net (code "81") (name "/USB2-DP") (class "Default")
      (node (ref "ESD-3") (pin "2") (pinfunction "2_2") (pintype "passive"))
      (node (ref "J1") (pin "90") (pinfunction "USB-DP2_90") (pintype "passive"))
      (node (ref "P3") (pin "3") (pinfunction "D+_3") (pintype "bidirectional"))
    )
    (net (code "82") (name "/USB3-DM") (class "Default")
      (node (ref "ESD-6") (pin "2") (pinfunction "2_2") (pintype "passive"))
      (node (ref "J1") (pin "87") (pinfunction "USB-DM3_87") (pintype "passive"))
      (node (ref "P4") (pin "2") (pinfunction "D-_2") (pintype "bidirectional"))
    )
    (net (code "83") (name "/USB3-DP") (class "Default")
      (node (ref "ESD-5") (pin "2") (pinfunction "2_2") (pintype "passive"))
      (node (ref "J1") (pin "88") (pinfunction "USB-DP3_88") (pintype "passive"))
      (node (ref "P4") (pin "3") (pinfunction "D+_3") (pintype "bidirectional"))
    )
    (net (code "84") (name "/USR_LED") (class "Default")
      (node (ref "J1") (pin "43") (pinfunction "GPIOG11_43") (pintype "passive"))
      (node (ref "R16") (pin "1") (pinfunction "1_1") (pintype "passive"))
    )
    (net (code "85") (name "/XIN") (class "Default")
      (node (ref "2") (pin "1") (pinfunction "IN_A1_1") (pintype "passive"))
      (node (ref "2") (pin "4") (pinfunction "OUT_Y2#_4") (pintype "passive"))
      (node (ref "C11") (pin "2") (pinfunction "2_2") (pintype "passive"))
      (node (ref "R15") (pin "1") (pinfunction "1_1") (pintype "passive"))
      (node (ref "Y1") (pin "1") (pinfunction "XIN_1") (pintype "passive"))
    )
    (net (code "86") (name "/XOUT") (class "Default")
      (node (ref "2") (pin "3") (pinfunction "IN_A2_3") (pintype "passive"))
      (node (ref "C10") (pin "1") (pinfunction "1_1") (pintype "passive"))
      (node (ref "R15") (pin "2") (pinfunction "2_2") (pintype "passive"))
      (node (ref "Y1") (pin "3") (pinfunction "XOUT_3") (pintype "passive"))
    )
    (net (code "87") (name "AGND") (class "Default")
      (node (ref "*1") (pin "1") (pinfunction "STD_1") (pintype "passive"))
      (node (ref "*1") (pin "7") (pinfunction "GND_7") (pintype "passive"))
      (node (ref "C17") (pin "1") (pinfunction "1_1") (pintype "passive"))
      (node (ref "C22") (pin "1") (pinfunction "1_1") (pintype "passive"))
      (node (ref "C5") (pin "1") (pinfunction "1_1") (pintype "passive"))
      (node (ref "C6") (pin "1") (pinfunction "1_1") (pintype "passive"))
      (node (ref "C7") (pin "1") (pinfunction "1_1") (pintype "passive"))
      (node (ref "ESD-1") (pin "2") (pinfunction "2_2") (pintype "passive"))
      (node (ref "ESD-2") (pin "1") (pinfunction "1_1") (pintype "passive"))
      (node (ref "J1") (pin "22") (pinfunction "AGND_22") (pintype "passive"))
    )
    (net (code "88") (name "GND") (class "Default")
      (node (ref "1") (pin "1") (pinfunction "GND_1") (pintype "passive"))
      (node (ref "1") (pin "6") (pinfunction "GND_6") (pintype "passive"))
      (node (ref "2") (pin "2") (pinfunction "GND_2") (pintype "passive"))
      (node (ref "3") (pin "7") (pinfunction "VSS_7") (pintype "passive"))
      (node (ref "C10") (pin "2") (pinfunction "2_2") (pintype "passive"))
      (node (ref "C11") (pin "1") (pinfunction "1_1") (pintype "passive"))
      (node (ref "C12") (pin "1") (pinfunction "1_1") (pintype "passive"))
      (node (ref "C13") (pin "1") (pinfunction "1_1") (pintype "passive"))
      (node (ref "C14") (pin "1") (pinfunction "1_1") (pintype "passive"))
      (node (ref "C15") (pin "1") (pinfunction "1_1") (pintype "passive"))
      (node (ref "C16") (pin "1") (pinfunction "1_1") (pintype "passive"))
      (node (ref "C2") (pin "1") (pinfunction "1_1") (pintype "passive"))
      (node (ref "C20") (pin "2") (pinfunction "2_2") (pintype "passive"))
      (node (ref "C23") (pin "1") (pinfunction "1_1") (pintype "passive"))
      (node (ref "C24") (pin "2") (pinfunction "2_2") (pintype "passive"))
      (node (ref "C25") (pin "2") (pinfunction "2_2") (pintype "passive"))
      (node (ref "C26") (pin "2") (pinfunction "2_2") (pintype "passive"))
      (node (ref "C27") (pin "1") (pinfunction "1_1") (pintype "passive"))
      (node (ref "C3") (pin "1") (pinfunction "1_1") (pintype "passive"))
      (node (ref "C4") (pin "1") (pinfunction "1_1") (pintype "passive"))
      (node (ref "C8") (pin "1") (pinfunction "1_1") (pintype "passive"))
      (node (ref "C9") (pin "1") (pinfunction "1_1") (pintype "passive"))
      (node (ref "D1") (pin "2") (pinfunction "K_2") (pintype "passive"))
      (node (ref "D2") (pin "2") (pinfunction "K_2") (pintype "passive"))
      (node (ref "D3") (pin "2") (pinfunction "K_2") (pintype "passive"))
      (node (ref "E1") (pin "3") (pinfunction "Gnd_3") (pintype "passive"))
      (node (ref "E1") (pin "8") (pinfunction "Gnd_8") (pintype "passive"))
      (node (ref "E2") (pin "3") (pinfunction "Gnd_3") (pintype "passive"))
      (node (ref "E2") (pin "8") (pinfunction "Gnd_8") (pintype "passive"))
      (node (ref "ESD-3") (pin "1") (pinfunction "1_1") (pintype "passive"))
      (node (ref "ESD-4") (pin "1") (pinfunction "1_1") (pintype "passive"))
      (node (ref "ESD-5") (pin "1") (pinfunction "1_1") (pintype "passive"))
      (node (ref "ESD-6") (pin "1") (pinfunction "1_1") (pintype "passive"))
      (node (ref "J1") (pin "45") (pinfunction "GND_45") (pintype "passive"))
      (node (ref "J1") (pin "46") (pinfunction "GND_46") (pintype "passive"))
      (node (ref "J1") (pin "47") (pinfunction "GND_47") (pintype "passive"))
      (node (ref "J1") (pin "48") (pinfunction "GND_48") (pintype "passive"))
      (node (ref "J1") (pin "49") (pinfunction "GND_49") (pintype "passive"))
      (node (ref "J1") (pin "70") (pinfunction "GND_70") (pintype "passive"))
      (node (ref "J2") (pin "15") (pinfunction "15_15") (pintype "passive"))
      (node (ref "J2") (pin "2") (pinfunction "2_2") (pintype "passive"))
      (node (ref "J3") (pin "10") (pinfunction "TMDS_DATA0_SHIELD_10") (pintype "passive"))
      (node (ref "J3") (pin "13") (pinfunction "TMDS_CLOCK_SHIELD_13") (pintype "passive"))
      (node (ref "J3") (pin "16") (pinfunction "DDC/CEC_GROUND_16") (pintype "passive"))
      (node (ref "J3") (pin "4") (pinfunction "TMDS_DATA2_SHIELD_4") (pintype "passive"))
      (node (ref "J3") (pin "7") (pinfunction "TMDS_DATA1_SHIELD_7") (pintype "passive"))
      (node (ref "J3") (pin "S1") (pinfunction "SHIELD_S1") (pintype "passive"))
      (node (ref "J3") (pin "S2") (pinfunction "SHIELD_S2") (pintype "passive"))
      (node (ref "J3") (pin "S3") (pinfunction "SHIELD_S3") (pintype "passive"))
      (node (ref "J3") (pin "S4") (pinfunction "SHIELD_S4") (pintype "passive"))
      (node (ref "K1") (pin "1") (pinfunction "1_1") (pintype "passive"))
      (node (ref "K2") (pin "1") (pinfunction "1_1") (pintype "passive"))
      (node (ref "P2") (pin "1") (pinfunction "1_1") (pintype "passive"))
      (node (ref "P2") (pin "2") (pinfunction "2_2") (pintype "passive"))
      (node (ref "P3") (pin "4") (pinfunction "GND_4") (pintype "passive"))
      (node (ref "P3") (pin "5") (pinfunction "SHIELD_5") (pintype "passive"))
      (node (ref "P3") (pin "6") (pinfunction "SHIELD_6") (pintype "passive"))
      (node (ref "P3") (pin "7") (pinfunction "SHIELD_7") (pintype "passive"))
      (node (ref "P4") (pin "4") (pinfunction "GND_4") (pintype "passive"))
      (node (ref "P4") (pin "5") (pinfunction "SHIELD_5") (pintype "passive"))
      (node (ref "P4") (pin "6") (pinfunction "SHIELD_6") (pintype "passive"))
      (node (ref "P4") (pin "7") (pinfunction "SHIELD_7") (pintype "passive"))
      (node (ref "R20") (pin "1") (pinfunction "1_1") (pintype "passive"))
      (node (ref "R23") (pin "1") (pinfunction "1_1") (pintype "passive"))
      (node (ref "R28") (pin "1") (pinfunction "1_1") (pintype "passive"))
      (node (ref "TF1") (pin "10") (pinfunction "GND_10") (pintype "passive"))
      (node (ref "TF1") (pin "6") (pinfunction "VSS_6") (pintype "passive"))
      (node (ref "U1") (pin "2") (pinfunction "GND_2") (pintype "passive"))
      (node (ref "U2") (pin "2") (pinfunction "GND_2") (pintype "passive"))
      (node (ref "U3") (pin "2") (pinfunction "GND_2") (pintype "passive"))
      (node (ref "U4") (pin "29") (pinfunction "HEAT_TAB_29") (pintype "passive"))
      (node (ref "U4") (pin "3") (pinfunction "GND_3") (pintype "passive"))
      (node (ref "USB1") (pin "1") (pinfunction "SH1_1") (pintype "passive"))
      (node (ref "USB1") (pin "2") (pinfunction "SH2_2") (pintype "passive"))
      (node (ref "USB1") (pin "3") (pinfunction "SH3_3") (pintype "passive"))
      (node (ref "USB1") (pin "4") (pinfunction "SH4_4") (pintype "passive"))
      (node (ref "USB1") (pin "A1") (pinfunction "GND_A1") (pintype "passive"))
      (node (ref "USB1") (pin "A12") (pinfunction "GND_A12") (pintype "passive"))
      (node (ref "USB1") (pin "B1") (pinfunction "GND_B1") (pintype "passive"))
      (node (ref "USB1") (pin "B12") (pinfunction "GND_B12") (pintype "passive"))
      (node (ref "Y1") (pin "2") (pinfunction "GND_2") (pintype "passive"))
      (node (ref "Y1") (pin "4") (pinfunction "GND_4") (pintype "passive"))
    )
    (net (code "89") (name "Net-(*1-BYS)") (class "Default")
      (node (ref "*1") (pin "2") (pinfunction "BYS_2") (pintype "passive"))
      (node (ref "*1") (pin "3") (pinfunction "IN+_3") (pintype "passive"))
      (node (ref "C7") (pin "2") (pinfunction "2_2") (pintype "passive"))
    )
    (net (code "90") (name "Net-(*1-IN-)") (class "Default")
      (node (ref "*1") (pin "4") (pinfunction "IN-_4") (pintype "passive"))
      (node (ref "R5") (pin "2") (pinfunction "2_2") (pintype "passive"))
      (node (ref "R6") (pin "1") (pinfunction "1_1") (pintype "passive"))
    )
    (net (code "91") (name "Net-(1-ANT)") (class "Default")
      (node (ref "1") (pin "5") (pinfunction "ANT_5") (pintype "passive"))
      (node (ref "A1") (pin "1") (pinfunction "1_1") (pintype "passive"))
    )
    (net (code "92") (name "Net-(2-OUT_Y1#)") (class "Default")
      (node (ref "2") (pin "6") (pinfunction "OUT_Y1#_6") (pintype "passive"))
      (node (ref "R11") (pin "1") (pinfunction "1_1") (pintype "passive"))
    )
    (net (code "93") (name "Net-(3-C1N)") (class "Default")
      (node (ref "3") (pin "4") (pinfunction "C1N_4") (pintype "passive"))
      (node (ref "C19") (pin "2") (pinfunction "2_2") (pintype "passive"))
    )
    (net (code "94") (name "Net-(3-C1P)") (class "Default")
      (node (ref "3") (pin "3") (pinfunction "C1P_3") (pintype "passive"))
      (node (ref "C19") (pin "1") (pinfunction "1_1") (pintype "passive"))
    )
    (net (code "95") (name "Net-(3-C2N)") (class "Default")
      (node (ref "3") (pin "2") (pinfunction "C2N_2") (pintype "passive"))
      (node (ref "C18") (pin "1") (pinfunction "1_1") (pintype "passive"))
    )
    (net (code "96") (name "Net-(3-C2P)") (class "Default")
      (node (ref "3") (pin "1") (pinfunction "C2P_1") (pintype "passive"))
      (node (ref "C18") (pin "2") (pinfunction "2_2") (pintype "passive"))
    )
    (net (code "97") (name "Net-(3-IREF)") (class "Default")
      (node (ref "3") (pin "12") (pinfunction "IREF_12") (pintype "passive"))
      (node (ref "R20") (pin "2") (pinfunction "2_2") (pintype "passive"))
    )
    (net (code "98") (name "Net-(3-VCC)") (class "Default")
      (node (ref "3") (pin "14") (pinfunction "VCC_14") (pintype "passive"))
      (node (ref "C15") (pin "2") (pinfunction "2_2") (pintype "passive"))
    )
    (net (code "99") (name "Net-(3-VCOMH)") (class "Default")
      (node (ref "3") (pin "13") (pinfunction "VCOMH_13") (pintype "passive"))
      (node (ref "C20") (pin "1") (pinfunction "1_1") (pintype "passive"))
    )
    (net (code "100") (name "Net-(C1-Pad1)") (class "Default")
      (node (ref "C1") (pin "1") (pinfunction "1_1") (pintype "passive"))
      (node (ref "R5") (pin "1") (pinfunction "1_1") (pintype "passive"))
    )
    (net (code "101") (name "Net-(C5-Pad2)") (class "Default")
      (node (ref "C5") (pin "2") (pinfunction "2_2") (pintype "passive"))
      (node (ref "R7") (pin "1") (pinfunction "1_1") (pintype "passive"))
    )
    (net (code "102") (name "Net-(D1-A)") (class "Default")
      (node (ref "D1") (pin "1") (pinfunction "A_1") (pintype "passive"))
      (node (ref "R13") (pin "2") (pinfunction "2_2") (pintype "passive"))
    )
    (net (code "103") (name "Net-(D2-A)") (class "Default")
      (node (ref "D2") (pin "1") (pinfunction "A_1") (pintype "passive"))
      (node (ref "R14") (pin "2") (pinfunction "2_2") (pintype "passive"))
    )
    (net (code "104") (name "Net-(D3-A)") (class "Default")
      (node (ref "D3") (pin "1") (pinfunction "A_1") (pintype "passive"))
      (node (ref "R16") (pin "2") (pinfunction "2_2") (pintype "passive"))
    )
    (net (code "105") (name "Net-(D5-K)") (class "Default")
      (node (ref "C25") (pin "1") (pinfunction "1_1") (pintype "passive"))
      (node (ref "D5") (pin "2") (pinfunction "K_2") (pintype "passive"))
      (node (ref "J3") (pin "19") (pinfunction "+5V_19") (pintype "passive"))
    )
    (net (code "106") (name "Net-(D6-K)") (class "Default")
      (node (ref "D6") (pin "2") (pinfunction "K_2") (pintype "passive"))
      (node (ref "R32") (pin "2") (pinfunction "2_2") (pintype "passive"))
    )
    (net (code "107") (name "Net-(J1-CAM_HSYNC)") (class "Default")
      (node (ref "J1") (pin "72") (pinfunction "CAM_HSYNC_72") (pintype "passive"))
      (node (ref "R4") (pin "2") (pinfunction "2_2") (pintype "passive"))
    )
    (net (code "108") (name "Net-(J1-CAM_MCLK)") (class "Default")
      (node (ref "J1") (pin "73") (pinfunction "CAM_MCLK_73") (pintype "passive"))
      (node (ref "R3") (pin "2") (pinfunction "2_2") (pintype "passive"))
    )
    (net (code "109") (name "Net-(J1-CAM_PCLK)") (class "Default")
      (node (ref "J1") (pin "74") (pinfunction "CAM_PCLK_74") (pintype "passive"))
      (node (ref "R2") (pin "2") (pinfunction "2_2") (pintype "passive"))
    )
    (net (code "110") (name "Net-(J1-CAM_VSYNC)") (class "Default")
      (node (ref "J1") (pin "75") (pinfunction "CAM_VSYNC_75") (pintype "passive"))
      (node (ref "R1") (pin "2") (pinfunction "2_2") (pintype "passive"))
    )
    (net (code "111") (name "Net-(J3-HOT_PLUG_DETECT)") (class "Default")
      (node (ref "C23") (pin "2") (pinfunction "2_2") (pintype "passive"))
      (node (ref "J3") (pin "1") (pinfunction "HOT_PLUG_DETECT_1") (pintype "passive"))
      (node (ref "R23") (pin "2") (pinfunction "2_2") (pintype "passive"))
      (node (ref "R24") (pin "1") (pinfunction "1_1") (pintype "passive"))
    )
    (net (code "112") (name "Net-(J4-1)") (class "Default")
      (node (ref "J4") (pin "8") (pinfunction "1_8") (pintype "passive"))
      (node (ref "R28") (pin "2") (pinfunction "2_2") (pintype "passive"))
    )
    (net (code "113") (name "Net-(J4-4)") (class "Default")
      (node (ref "C26") (pin "1") (pinfunction "1_1") (pintype "passive"))
      (node (ref "J4") (pin "5") (pinfunction "4_5") (pintype "passive"))
    )
    (net (code "114") (name "Net-(J4-5)") (class "Default")
      (node (ref "C24") (pin "1") (pinfunction "1_1") (pintype "passive"))
      (node (ref "J4") (pin "4") (pinfunction "5_4") (pintype "passive"))
    )
    (net (code "115") (name "Net-(J4-9)") (class "Default")
      (node (ref "J4") (pin "12") (pinfunction "9_12") (pintype "passive"))
      (node (ref "R30") (pin "2") (pinfunction "2_2") (pintype "passive"))
    )
    (net (code "116") (name "Net-(J4-11)") (class "Default")
      (node (ref "J4") (pin "10") (pinfunction "11_10") (pintype "passive"))
      (node (ref "R31") (pin "2") (pinfunction "2_2") (pintype "passive"))
    )
    (net (code "117") (name "Net-(U1-BYPASS)") (class "Default")
      (node (ref "C4") (pin "2") (pinfunction "2_2") (pintype "passive"))
      (node (ref "U1") (pin "4") (pinfunction "BYPASS_4") (pintype "passive"))
    )
    (net (code "118") (name "Net-(U3-VOUT2)") (class "Default")
      (node (ref "C13") (pin "2") (pinfunction "2_2") (pintype "passive"))
      (node (ref "U3") (pin "1") (pinfunction "VOUT2_1") (pintype "passive"))
    )
    (net (code "119") (name "Net-(U4-*RST)") (class "Default")
      (node (ref "R27") (pin "2") (pinfunction "2_2") (pintype "passive"))
      (node (ref "U4") (pin "9") (pinfunction "*RST_9") (pintype "passive"))
    )
    (net (code "120") (name "Net-(U4-TXD)") (class "Default")
      (node (ref "R29") (pin "2") (pinfunction "2_2") (pintype "passive"))
      (node (ref "U4") (pin "26") (pinfunction "TXD_26") (pintype "passive"))
    )
    (net (code "121") (name "VDD_1V5") (class "Default")
      (node (ref "C9") (pin "2") (pinfunction "2_2") (pintype "passive"))
      (node (ref "J2") (pin "10") (pinfunction "10_10") (pintype "passive"))
      (node (ref "U2") (pin "6") (pinfunction "VOUT1_6") (pintype "passive"))
    )
    (net (code "122") (name "VDD_2V8") (class "Default")
      (node (ref "C8") (pin "2") (pinfunction "2_2") (pintype "passive"))
      (node (ref "J2") (pin "4") (pinfunction "4_4") (pintype "passive"))
      (node (ref "U2") (pin "1") (pinfunction "VOUT2_1") (pintype "passive"))
    )
    (net (code "123") (name "VDD_3V") (class "Default")
      (node (ref "2") (pin "5") (pinfunction "VCC_5") (pintype "passive"))
      (node (ref "C14") (pin "2") (pinfunction "2_2") (pintype "passive"))
      (node (ref "J2") (pin "11") (pinfunction "11_11") (pintype "passive"))
      (node (ref "J2") (pin "23") (pinfunction "23_23") (pintype "passive"))
      (node (ref "R8") (pin "2") (pinfunction "2_2") (pintype "passive"))
      (node (ref "R9") (pin "2") (pinfunction "2_2") (pintype "passive"))
      (node (ref "U3") (pin "6") (pinfunction "VOUT1_6") (pintype "passive"))
    )
    (net (code "124") (name "VDD_3V3") (class "Default")
      (node (ref "1") (pin "4") (pinfunction "VBUS_4") (pintype "passive"))
      (node (ref "3") (pin "5") (pinfunction "VBAT_5") (pintype "passive"))
      (node (ref "3") (pin "8") (pinfunction "VDD_8") (pintype "passive"))
      (node (ref "4") (pin "1") (pinfunction "G_1") (pintype "passive"))
      (node (ref "C12") (pin "2") (pinfunction "2_2") (pintype "passive"))
      (node (ref "C2") (pin "2") (pinfunction "2_2") (pintype "passive"))
      (node (ref "C3") (pin "2") (pinfunction "2_2") (pintype "passive"))
      (node (ref "D4") (pin "2") (pinfunction "K_2") (pintype "passive"))
      (node (ref "D6") (pin "1") (pinfunction "A_1") (pintype "passive"))
      (node (ref "R10") (pin "1") (pinfunction "1_1") (pintype "passive"))
      (node (ref "R12") (pin "1") (pinfunction "1_1") (pintype "passive"))
      (node (ref "R17") (pin "1") (pinfunction "1_1") (pintype "passive"))
      (node (ref "R21") (pin "2") (pinfunction "2_2") (pintype "passive"))
      (node (ref "R26") (pin "2") (pinfunction "2_2") (pintype "passive"))
      (node (ref "R33") (pin "2") (pinfunction "2_2") (pintype "passive"))
      (node (ref "TF1") (pin "4") (pinfunction "VDD_4") (pintype "passive"))
      (node (ref "U1") (pin "5") (pinfunction "VOUT_5") (pintype "passive"))
    )
    (net (code "125") (name "VDD_5V") (class "Default")
      (node (ref "*1") (pin "6") (pinfunction "VCC_6") (pintype "passive"))
      (node (ref "C6") (pin "2") (pinfunction "2_2") (pintype "passive"))
      (node (ref "D5") (pin "1") (pinfunction "A_1") (pintype "passive"))
      (node (ref "J1") (pin "68") (pinfunction "VDD_5V_68") (pintype "passive"))
      (node (ref "J1") (pin "69") (pinfunction "VDD_5V_69") (pintype "passive"))
      (node (ref "P2") (pin "4") (pinfunction "4_4") (pintype "passive"))
      (node (ref "P2") (pin "6") (pinfunction "6_6") (pintype "passive"))
      (node (ref "P3") (pin "1") (pinfunction "VBUS_1") (pintype "power_in"))
      (node (ref "P4") (pin "1") (pinfunction "VBUS_1") (pintype "power_in"))
      (node (ref "R18") (pin "2") (pinfunction "2_2") (pintype "passive"))
      (node (ref "R22") (pin "2") (pinfunction "2_2") (pintype "passive"))
      (node (ref "R27") (pin "1") (pinfunction "1_1") (pintype "passive"))
      (node (ref "R30") (pin "1") (pinfunction "1_1") (pintype "passive"))
      (node (ref "R31") (pin "1") (pinfunction "1_1") (pintype "passive"))
      (node (ref "U1") (pin "1") (pinfunction "VIN_1") (pintype "passive"))
      (node (ref "U1") (pin "3") (pinfunction "ON/OFF_3") (pintype "passive"))
      (node (ref "U2") (pin "3") (pinfunction "EN2_3") (pintype "passive"))
      (node (ref "U2") (pin "4") (pinfunction "EN1_4") (pintype "passive"))
      (node (ref "U2") (pin "5") (pinfunction "VIN_5") (pintype "passive"))
      (node (ref "U3") (pin "3") (pinfunction "EN2_3") (pintype "passive"))
      (node (ref "U3") (pin "4") (pinfunction "EN1_4") (pintype "passive"))
      (node (ref "U3") (pin "5") (pinfunction "VIN_5") (pintype "passive"))
      (node (ref "U4") (pin "7") (pinfunction "REGIN_7") (pintype "passive"))
      (node (ref "U4") (pin "8") (pinfunction "VBUS_8") (pintype "passive"))
      (node (ref "USB1") (pin "A4") (pinfunction "VBUS_A4") (pintype "passive"))
      (node (ref "USB1") (pin "A9") (pinfunction "VBUS_A9") (pintype "passive"))
      (node (ref "USB1") (pin "B4") (pinfunction "VBUS_B4") (pintype "passive"))
      (node (ref "USB1") (pin "B9") (pinfunction "VBUS_B9") (pintype "passive"))
    )
    (net (code "126") (name "unconnected-(3-VBREF-Pad6)") (class "Default")
      (node (ref "3") (pin "6") (pinfunction "VBREF_6") (pintype "passive"))
    )
    (net (code "127") (name "unconnected-(J1-GPIOL3{slash}K1-Pad97)") (class "Default")
      (node (ref "J1") (pin "97") (pinfunction "GPIOL3/K1_97") (pintype "passive"))
    )
    (net (code "128") (name "unconnected-(J1-GPIOL4{slash}RECOVERY-Pad96)") (class "Default")
      (node (ref "J1") (pin "96") (pinfunction "GPIOL4/RECOVERY_96") (pintype "passive"))
    )
    (net (code "129") (name "unconnected-(J1-IR-RX-Pad26)") (class "Default")
      (node (ref "J1") (pin "26") (pinfunction "IR-RX_26") (pintype "passive"))
    )
    (net (code "130") (name "unconnected-(J1-KEYADC-Pad25)") (class "Default")
      (node (ref "J1") (pin "25") (pinfunction "KEYADC_25") (pintype "passive"))
    )
    (net (code "131") (name "unconnected-(J1-LINEOUTR-Pad23)") (class "Default")
      (node (ref "J1") (pin "23") (pinfunction "LINEOUTR_23") (pintype "passive"))
    )
    (net (code "132") (name "unconnected-(J1-UART1_CTS-Pad32)") (class "Default")
      (node (ref "J1") (pin "32") (pinfunction "UART1_CTS_32") (pintype "passive"))
    )
    (net (code "133") (name "unconnected-(J1-UART1_RTS-Pad31)") (class "Default")
      (node (ref "J1") (pin "31") (pinfunction "UART1_RTS_31") (pintype "passive"))
    )
    (net (code "134") (name "unconnected-(J1-UART2_CTS-Pad38)") (class "Default")
      (node (ref "J1") (pin "38") (pinfunction "UART2_CTS_38") (pintype "passive"))
    )
    (net (code "135") (name "unconnected-(J1-UART2_RTS-Pad35)") (class "Default")
      (node (ref "J1") (pin "35") (pinfunction "UART2_RTS_35") (pintype "passive"))
    )
    (net (code "136") (name "unconnected-(J1-UART3_CTS-Pad41)") (class "Default")
      (node (ref "J1") (pin "41") (pinfunction "UART3_CTS_41") (pintype "passive"))
    )
    (net (code "137") (name "unconnected-(J1-UART3_RTS-Pad42)") (class "Default")
      (node (ref "J1") (pin "42") (pinfunction "UART3_RTS_42") (pintype "passive"))
    )
    (net (code "138") (name "unconnected-(J1-USB0-DRVVBUS-Pad18)") (class "Default")
      (node (ref "J1") (pin "18") (pinfunction "USB0-DRVVBUS_18") (pintype "passive"))
    )
    (net (code "139") (name "unconnected-(J1-VDD_SYS_3V3-Pad65)") (class "Default")
      (node (ref "J1") (pin "65") (pinfunction "VDD_SYS_3V3_65") (pintype "passive"))
    )
    (net (code "140") (name "unconnected-(J1-VDD_USB_5V-Pad66)") (class "Default")
      (node (ref "J1") (pin "66") (pinfunction "VDD_USB_5V_66") (pintype "passive"))
    )
    (net (code "141") (name "unconnected-(J1-VDD_USB_5V-Pad67)") (class "Default")
      (node (ref "J1") (pin "67") (pinfunction "VDD_USB_5V_67") (pintype "passive"))
    )
    (net (code "142") (name "unconnected-(J2-Pad1)") (class "Default")
      (node (ref "J2") (pin "1") (pinfunction "1_1") (pintype "passive"))
    )
    (net (code "143") (name "unconnected-(J2-Pad24)") (class "Default")
      (node (ref "J2") (pin "24") (pinfunction "24_24") (pintype "passive"))
    )
    (net (code "144") (name "unconnected-(J3-UTILITY-Pad2)") (class "Default")
      (node (ref "J3") (pin "2") (pinfunction "UTILITY_2") (pintype "passive"))
    )
    (net (code "145") (name "unconnected-(J4-2-Pad7)") (class "Default")
      (node (ref "J4") (pin "7") (pinfunction "2_7") (pintype "passive"))
    )
    (net (code "146") (name "unconnected-(J4-SHIELD-PadSHELL1)") (class "Default")
      (node (ref "J4") (pin "SHELL1") (pinfunction "SHIELD_SHELL1") (pintype "passive"))
    )
    (net (code "147") (name "unconnected-(J4-SHIELD-PadSHELL2)") (class "Default")
      (node (ref "J4") (pin "SHELL2") (pinfunction "SHIELD_SHELL2") (pintype "passive"))
    )
    (net (code "148") (name "unconnected-(U4-*SUSPEND-Pad11)") (class "Default")
      (node (ref "U4") (pin "11") (pinfunction "*SUSPEND_11") (pintype "passive"))
    )
    (net (code "149") (name "unconnected-(U4-CTS-Pad23)") (class "Default")
      (node (ref "U4") (pin "23") (pinfunction "CTS_23") (pintype "passive"))
    )
    (net (code "150") (name "unconnected-(U4-DCD-Pad1)") (class "Default")
      (node (ref "U4") (pin "1") (pinfunction "DCD_1") (pintype "passive"))
    )
    (net (code "151") (name "unconnected-(U4-DSR-Pad27)") (class "Default")
      (node (ref "U4") (pin "27") (pinfunction "DSR_27") (pintype "passive"))
    )
    (net (code "152") (name "unconnected-(U4-DTR-Pad28)") (class "Default")
      (node (ref "U4") (pin "28") (pinfunction "DTR_28") (pintype "passive"))
    )
    (net (code "153") (name "unconnected-(U4-NC-Pad10)") (class "Default")
      (node (ref "U4") (pin "10") (pinfunction "NC_10") (pintype "passive"))
    )
    (net (code "154") (name "unconnected-(U4-NC-Pad13)") (class "Default")
      (node (ref "U4") (pin "13") (pinfunction "NC_13") (pintype "passive"))
    )
    (net (code "155") (name "unconnected-(U4-NC-Pad14)") (class "Default")
      (node (ref "U4") (pin "14") (pinfunction "NC_14") (pintype "passive"))
    )
    (net (code "156") (name "unconnected-(U4-NC-Pad15)") (class "Default")
      (node (ref "U4") (pin "15") (pinfunction "NC_15") (pintype "passive"))
    )
    (net (code "157") (name "unconnected-(U4-NC-Pad16)") (class "Default")
      (node (ref "U4") (pin "16") (pinfunction "NC_16") (pintype "passive"))
    )
    (net (code "158") (name "unconnected-(U4-NC-Pad17)") (class "Default")
      (node (ref "U4") (pin "17") (pinfunction "NC_17") (pintype "passive"))
    )
    (net (code "159") (name "unconnected-(U4-NC-Pad18)") (class "Default")
      (node (ref "U4") (pin "18") (pinfunction "NC_18") (pintype "passive"))
    )
    (net (code "160") (name "unconnected-(U4-NC-Pad19)") (class "Default")
      (node (ref "U4") (pin "19") (pinfunction "NC_19") (pintype "passive"))
    )
    (net (code "161") (name "unconnected-(U4-NC-Pad20)") (class "Default")
      (node (ref "U4") (pin "20") (pinfunction "NC_20") (pintype "passive"))
    )
    (net (code "162") (name "unconnected-(U4-NC-Pad21)") (class "Default")
      (node (ref "U4") (pin "21") (pinfunction "NC_21") (pintype "passive"))
    )
    (net (code "163") (name "unconnected-(U4-NC-Pad22)") (class "Default")
      (node (ref "U4") (pin "22") (pinfunction "NC_22") (pintype "passive"))
    )
    (net (code "164") (name "unconnected-(U4-RI-Pad2)") (class "Default")
      (node (ref "U4") (pin "2") (pinfunction "RI_2") (pintype "passive"))
    )
    (net (code "165") (name "unconnected-(U4-RTS-Pad24)") (class "Default")
      (node (ref "U4") (pin "24") (pinfunction "RTS_24") (pintype "passive"))
    )
    (net (code "166") (name "unconnected-(U4-SUSPEND-Pad12)") (class "Default")
      (node (ref "U4") (pin "12") (pinfunction "SUSPEND_12") (pintype "passive"))
    )
    (net (code "167") (name "unconnected-(U4-VDD-Pad6)") (class "Default")
      (node (ref "U4") (pin "6") (pinfunction "VDD_6") (pintype "passive"))
    )
    (net (code "168") (name "unconnected-(USB1-RX1+-PadB11)") (class "Default")
      (node (ref "USB1") (pin "B11") (pinfunction "RX1+_B11") (pintype "passive"))
    )
    (net (code "169") (name "unconnected-(USB1-RX1--PadB10)") (class "Default")
      (node (ref "USB1") (pin "B10") (pinfunction "RX1-_B10") (pintype "passive"))
    )
    (net (code "170") (name "unconnected-(USB1-RX2+-PadA11)") (class "Default")
      (node (ref "USB1") (pin "A11") (pinfunction "RX2+_A11") (pintype "passive"))
    )
    (net (code "171") (name "unconnected-(USB1-RX2--PadA10)") (class "Default")
      (node (ref "USB1") (pin "A10") (pinfunction "RX2-_A10") (pintype "passive"))
    )
    (net (code "172") (name "unconnected-(USB1-SBU1-PadA8)") (class "Default")
      (node (ref "USB1") (pin "A8") (pinfunction "SBU1_A8") (pintype "passive"))
    )
    (net (code "173") (name "unconnected-(USB1-SBU2-PadB8)") (class "Default")
      (node (ref "USB1") (pin "B8") (pinfunction "SBU2_B8") (pintype "passive"))
    )
    (net (code "174") (name "unconnected-(USB1-TX1+-PadA2)") (class "Default")
      (node (ref "USB1") (pin "A2") (pinfunction "TX1+_A2") (pintype "passive"))
    )
    (net (code "175") (name "unconnected-(USB1-TX1--PadA3)") (class "Default")
      (node (ref "USB1") (pin "A3") (pinfunction "TX1-_A3") (pintype "passive"))
    )
    (net (code "176") (name "unconnected-(USB1-TX2+-PadB2)") (class "Default")
      (node (ref "USB1") (pin "B2") (pinfunction "TX2+_B2") (pintype "passive"))
    )
    (net (code "177") (name "unconnected-(USB1-TX2--PadB3)") (class "Default")
      (node (ref "USB1") (pin "B3") (pinfunction "TX2-_B3") (pintype "passive"))
    )
  )
)
